# nerdstern.net
KiCad netlist of a schematic drawn in EAGLE
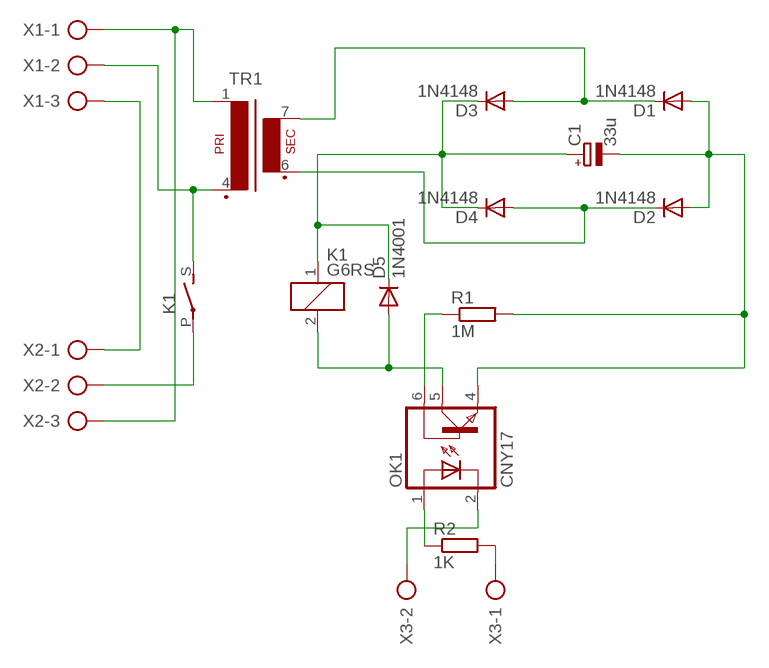
[diagram p0: schematic, sheet 1]

(export (version "E")
  (design (tool "Eeschema 10.0.6"))
  (components
    (comp (ref "C1")
      (value "33u")
      (footprint "eagle-import:E2-5")
      (libsource (lib "eagle-import") (part "CPOL-EUE2-5"))
    )
    (comp (ref "D1")
      (value "1N4148")
      (footprint "eagle-import:DO35-7")
      (libsource (lib "eagle-import") (part "1N4148DO35-7"))
    )
    (comp (ref "D2")
      (value "1N4148")
      (footprint "eagle-import:DO35-7")
      (libsource (lib "eagle-import") (part "1N4148DO35-7"))
    )
    (comp (ref "D3")
      (value "1N4148")
      (footprint "eagle-import:DO35-7")
      (libsource (lib "eagle-import") (part "1N4148DO35-7"))
    )
    (comp (ref "D4")
      (value "1N4148")
      (footprint "eagle-import:DO35-7")
      (libsource (lib "eagle-import") (part "1N4148DO35-7"))
    )
    (comp (ref "D5")
      (value "1N4001")
      (footprint "eagle-import:DO35-7")
      (libsource (lib "eagle-import") (part "1N4148DO35-7"))
    )
    (comp (ref "K1")
      (value "G6RS")
      (footprint "eagle-import:G6RS")
      (libsource (lib "eagle-import") (part "G6RS"))
    )
    (comp (ref "OK1")
      (value "CNY17")
      (footprint "eagle-import:DIL06")
      (fields (field (name "MPN") "CNY17-1"))
      (libsource (lib "eagle-import") (part "CNY17"))
    )
    (comp (ref "R1")
      (value "1M")
      (footprint "eagle-import:0204_5")
      (libsource (lib "eagle-import") (part "R-EU_0204/5"))
    )
    (comp (ref "R2")
      (value "1K")
      (footprint "eagle-import:0204_5")
      (libsource (lib "eagle-import") (part "R-EU_0204/5"))
    )
    (comp (ref "TR1")
      (value "EE20-1")
      (footprint "eagle-import:EE20-1")
      (libsource (lib "eagle-import") (part "EE20-1"))
    )
    (comp (ref "X1")
      (value "AK500/3")
      (footprint "eagle-import:AK500_3")
      (libsource (lib "eagle-import") (part "AK500/3"))
    )
    (comp (ref "X2")
      (value "AK500/3")
      (footprint "eagle-import:AK500_3")
      (libsource (lib "eagle-import") (part "AK500/3"))
    )
    (comp (ref "X3")
      (value "AK500/2")
      (footprint "eagle-import:AK500_2")
      (libsource (lib "eagle-import") (part "AK500/2"))
    )
  )
  (nets
    (net (code "1") (name "Net-(C1-Pad+)") (class "Default")
      (node (ref "C1") (pin "+") (pinfunction "+_+") (pintype "passive"))
      (node (ref "D3") (pin "C") (pinfunction "C_C") (pintype "passive"))
      (node (ref "D4") (pin "C") (pinfunction "C_C") (pintype "passive"))
      (node (ref "D5") (pin "C") (pinfunction "C_C") (pintype "passive"))
      (node (ref "K1") (pin "1") (pinfunction "1_1") (pintype "passive"))
    )
    (net (code "2") (name "Net-(OK1-A)") (class "Default")
      (node (ref "OK1") (pin "1") (pinfunction "A_1") (pintype "passive"))
      (node (ref "R2") (pin "1") (pinfunction "1_1") (pintype "passive"))
    )
    (net (code "3") (name "Net-(OK1-BAS)") (class "Default")
      (node (ref "OK1") (pin "6") (pinfunction "BAS_6") (pintype "passive"))
      (node (ref "R1") (pin "1") (pinfunction "1_1") (pintype "passive"))
    )
    (net (code "4") (name "Net-(OK1-C)") (class "Default")
      (node (ref "OK1") (pin "2") (pinfunction "C_2") (pintype "passive"))
      (node (ref "X3") (pin "2") (pinfunction "KL_2") (pintype "passive"))
    )
    (net (code "5") (name "Net-(OK1-COL)") (class "Default")
      (node (ref "D5") (pin "A") (pinfunction "A_A") (pintype "passive"))
      (node (ref "K1") (pin "2") (pinfunction "2_2") (pintype "passive"))
      (node (ref "OK1") (pin "5") (pinfunction "COL_5") (pintype "passive"))
    )
    (net (code "6") (name "Net-(OK1-EMI)") (class "Default")
      (node (ref "C1") (pin "-") (pinfunction "-_-") (pintype "passive"))
      (node (ref "D1") (pin "A") (pinfunction "A_A") (pintype "passive"))
      (node (ref "D2") (pin "A") (pinfunction "A_A") (pintype "passive"))
      (node (ref "OK1") (pin "4") (pinfunction "EMI_4") (pintype "passive"))
      (node (ref "R1") (pin "2") (pinfunction "2_2") (pintype "passive"))
    )
    (net (code "7") (name "Net-(TR1-P1)") (class "Default")
      (node (ref "TR1") (pin "1") (pinfunction "P1_1") (pintype "passive"))
      (node (ref "X1") (pin "1") (pinfunction "KL_1") (pintype "passive"))
      (node (ref "X2") (pin "3") (pinfunction "KL_3") (pintype "passive"))
    )
    (net (code "8") (name "Net-(TR1-P2)") (class "Default")
      (node (ref "K1") (pin "S") (pinfunction "S_S") (pintype "passive"))
      (node (ref "TR1") (pin "4") (pinfunction "P2_4") (pintype "passive"))
      (node (ref "X1") (pin "2") (pinfunction "KL_2") (pintype "passive"))
    )
    (net (code "9") (name "Net-(TR1-S3)") (class "Default")
      (node (ref "D2") (pin "C") (pinfunction "C_C") (pintype "passive"))
      (node (ref "D4") (pin "A") (pinfunction "A_A") (pintype "passive"))
      (node (ref "TR1") (pin "6") (pinfunction "S3_6") (pintype "passive"))
    )
    (net (code "10") (name "Net-(TR1-S4)") (class "Default")
      (node (ref "D1") (pin "C") (pinfunction "C_C") (pintype "passive"))
      (node (ref "D3") (pin "A") (pinfunction "A_A") (pintype "passive"))
      (node (ref "TR1") (pin "7") (pinfunction "S4_7") (pintype "passive"))
    )
    (net (code "11") (name "Net-(X1C-KL)") (class "Default")
      (node (ref "X1") (pin "3") (pinfunction "KL_3") (pintype "passive"))
      (node (ref "X2") (pin "1") (pinfunction "KL_1") (pintype "passive"))
    )
    (net (code "12") (name "Net-(X2B-KL)") (class "Default")
      (node (ref "K1") (pin "P") (pinfunction "P_P") (pintype "passive"))
      (node (ref "X2") (pin "2") (pinfunction "KL_2") (pintype "passive"))
    )
    (net (code "13") (name "Net-(X3A-KL)") (class "Default")
      (node (ref "R2") (pin "2") (pinfunction "2_2") (pintype "passive"))
      (node (ref "X3") (pin "1") (pinfunction "KL_1") (pintype "passive"))
    )
  )
)
